# Power.net
KiCad netlist of a schematic drawn in Altium Designer
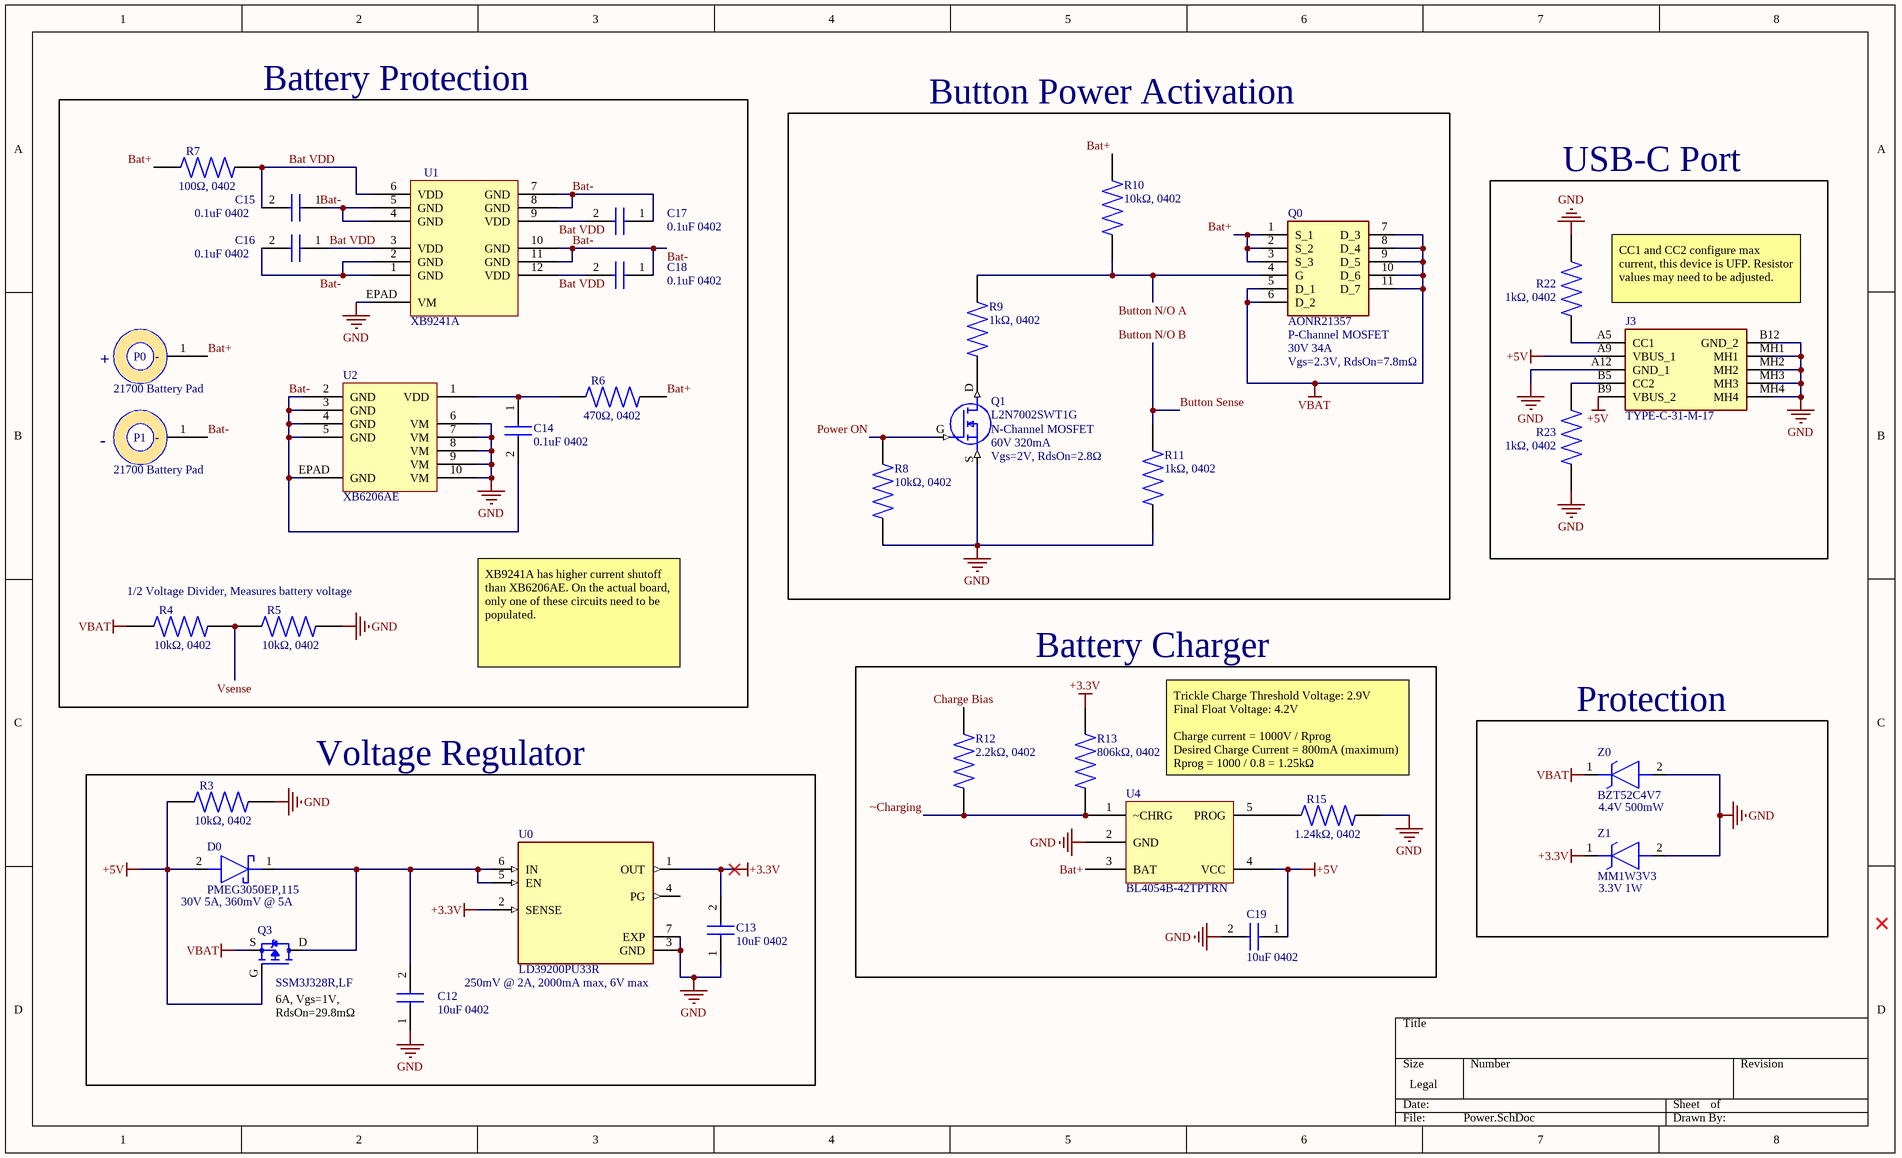
[diagram p0: Power.SchDoc]

(export (version "E")
  (design (tool "Eeschema 10.0.6"))
  (components
    (comp (ref "C12")
      (value "10uF 0402")
      (footprint "SamacSys:CAPC1005X56N")
      (description "Capacitor")
      (fields
        (field (name "MANUFACTURER_PART_NUMBER") "04025A100BAT2A")
        (field (name "MOUSER PART NUMBER") "581-04025A100B")
      )
      (libsource (lib "*") (part "04025A100BAT2A"))
    )
    (comp (ref "C13")
      (value "10uF 0402")
      (footprint "SamacSys:CAPC1005X56N")
      (description "Capacitor")
      (fields
        (field (name "MANUFACTURER_PART_NUMBER") "04025A100BAT2A")
        (field (name "MOUSER PART NUMBER") "581-04025A100B")
      )
      (libsource (lib "*") (part "04025A100BAT2A"))
    )
    (comp (ref "C14")
      (value "0.1uF 0402")
      (footprint "SamacSys:CAPC1005X56N")
      (description "Capacitor")
      (fields
        (field (name "MANUFACTURER_PART_NUMBER") "04025A100BAT2A")
        (field (name "MOUSER PART NUMBER") "581-04025A100B")
      )
      (libsource (lib "*") (part "04025A100BAT2A"))
    )
    (comp (ref "C15")
      (value "0.1uF 0402")
      (footprint "SamacSys:CAPC1005X56N")
      (description "Capacitor")
      (fields
        (field (name "MANUFACTURER_PART_NUMBER") "04025A100BAT2A")
        (field (name "MOUSER PART NUMBER") "581-04025A100B")
      )
      (libsource (lib "*") (part "04025A100BAT2A"))
    )
    (comp (ref "C16")
      (value "0.1uF 0402")
      (footprint "SamacSys:CAPC1005X56N")
      (description "Capacitor")
      (fields
        (field (name "MANUFACTURER_PART_NUMBER") "04025A100BAT2A")
        (field (name "MOUSER PART NUMBER") "581-04025A100B")
      )
      (libsource (lib "*") (part "04025A100BAT2A"))
    )
    (comp (ref "C17")
      (value "0.1uF 0402")
      (footprint "SamacSys:CAPC1005X56N")
      (description "Capacitor")
      (fields
        (field (name "MANUFACTURER_PART_NUMBER") "04025A100BAT2A")
        (field (name "MOUSER PART NUMBER") "581-04025A100B")
      )
      (libsource (lib "*") (part "04025A100BAT2A"))
    )
    (comp (ref "C18")
      (value "0.1uF 0402")
      (footprint "SamacSys:CAPC1005X56N")
      (description "Capacitor")
      (fields
        (field (name "MANUFACTURER_PART_NUMBER") "04025A100BAT2A")
        (field (name "MOUSER PART NUMBER") "581-04025A100B")
      )
      (libsource (lib "*") (part "04025A100BAT2A"))
    )
    (comp (ref "C19")
      (value "10uF 0402")
      (footprint "SamacSys:CAPC1005X56N")
      (description "Capacitor")
      (fields
        (field (name "MANUFACTURER_PART_NUMBER") "04025A100BAT2A")
        (field (name "MOUSER PART NUMBER") "581-04025A100B")
      )
      (libsource (lib "*") (part "04025A100BAT2A"))
    )
    (comp (ref "D0")
      (value "PMEG3050EP,115")
      (footprint "Lightsaber PCB Library:SOD128")
      (description "Schottky Diode")
      (fields (field (name "MOUSER PART NUMBER") "771-PMEG3050EP115"))
      (libsource (lib "Lightsaber") (part "PMEG3050EP,115"))
    )
    (comp (ref "J3")
      (value "TYPE-C-31-M-17")
      (footprint "SamacSys:TYPEC31M17")
      (description "Connector")
      (libsource (lib "*") (part "TYPE-C-31-M-17"))
    )
    (comp (ref "P0")
      (value "21700 Battery Pad")
      (footprint "21700 Battery Pad")
      (libsource (lib "Lightsaber") (part "21700 Battery Pad"))
    )
    (comp (ref "P1")
      (value "21700 Battery Pad")
      (footprint "21700 Battery Pad")
      (libsource (lib "Lightsaber") (part "21700 Battery Pad"))
    )
    (comp (ref "Q0")
      (value "AONR21357")
      (footprint "SamacSys:AONR21357")
      (description "MOSFET (P-Channel)")
      (libsource (lib "*") (part "AONR21357"))
    )
    (comp (ref "Q1")
      (value "L2N7002SWT1G")
      (footprint "Lightsaber PCB Library:SC-70")
      (description "MOSFET (N-Channel)")
      (fields
        (field (name "MANUFACTURER_PART_NUMBER") "2N7000")
        (field (name "MOUSER PART NUMBER") "512-2N7000")
      )
      (libsource (lib "Lightsaber") (part "L2N7002SWT1G"))
    )
    (comp (ref "Q3")
      (value "SSM3J328R,LF")
      (footprint "SOT-23F")
      (description "P-Channel 20V 9.4A (Ta) 2.4W (Ta) Surface Mount 6-MicroFET (2x2)")
      (fields (field (name "MP") "FDMA910PZ") (field (name "MF") "{'manufacturer': u'ON Semiconductor'}"))
      (libsource (lib "Lightsaber") (part "SSM3J328R,LF"))
    )
    (comp (ref "R3")
      (value "10kΩ, 0402")
      (footprint "0402")
      (libsource (lib "Lightsaber") (part "Resistor, 0402"))
    )
    (comp (ref "R4")
      (value "10kΩ, 0402")
      (footprint "0402")
      (libsource (lib "Lightsaber") (part "Resistor, 0402"))
    )
    (comp (ref "R5")
      (value "10kΩ, 0402")
      (footprint "0402")
      (libsource (lib "Lightsaber") (part "Resistor, 0402"))
    )
    (comp (ref "R6")
      (value "470Ω, 0402")
      (footprint "0402")
      (libsource (lib "Lightsaber") (part "Resistor, 0402"))
    )
    (comp (ref "R7")
      (value "100Ω, 0402")
      (footprint "0402")
      (libsource (lib "Lightsaber") (part "Resistor, 0402"))
    )
    (comp (ref "R8")
      (value "10kΩ, 0402")
      (footprint "0402")
      (libsource (lib "Lightsaber") (part "Resistor, 0402"))
    )
    (comp (ref "R9")
      (value "1kΩ, 0402")
      (footprint "0402")
      (libsource (lib "Lightsaber") (part "Resistor, 0402"))
    )
    (comp (ref "R10")
      (value "10kΩ, 0402")
      (footprint "0402")
      (libsource (lib "Lightsaber") (part "Resistor, 0402"))
    )
    (comp (ref "R11")
      (value "1kΩ, 0402")
      (footprint "0402")
      (libsource (lib "Lightsaber") (part "Resistor, 0402"))
    )
    (comp (ref "R12")
      (value "2.2kΩ, 0402")
      (footprint "0402")
      (libsource (lib "Lightsaber") (part "Resistor, 0402"))
    )
    (comp (ref "R13")
      (value "806kΩ, 0402")
      (footprint "0402")
      (libsource (lib "Lightsaber") (part "Resistor, 0402"))
    )
    (comp (ref "R15")
      (value "1.24kΩ, 0402")
      (footprint "0402")
      (libsource (lib "Lightsaber") (part "Resistor, 0402"))
    )
    (comp (ref "R22")
      (value "1kΩ, 0402")
      (footprint "0402")
      (libsource (lib "Lightsaber") (part "Resistor, 0402"))
    )
    (comp (ref "R23")
      (value "1kΩ, 0402")
      (footprint "0402")
      (libsource (lib "Lightsaber") (part "Resistor, 0402"))
    )
    (comp (ref "U0")
      (value "LD39200PU33R")
      (footprint "LD39200PU33R:SON95P300X300X100-7N")
      (description "Linear Voltage Regulator IC 1 Output 2A 6-DFN (3x3)")
      (fields (field (name "MF") "{'manufacturer': u'STMicroelectronics'}"))
      (libsource (lib "*") (part "LD39200PU33R"))
    )
    (comp (ref "U1")
      (value "XB9241A")
      (footprint "DFN4x4x0.55-12FC")
      (libsource (lib "Lightsaber") (part "XB9241A"))
    )
    (comp (ref "U2")
      (value "XB6206AE")
      (footprint "DFN3X3-10")
      (libsource (lib "Lightsaber") (part "XB6206AE"))
    )
    (comp (ref "U4")
      (value "BL4054B-42TPTRN")
      (footprint "TSOT23-5")
      (libsource (lib "Lightsaber") (part "BL4054B-42TPTRN"))
    )
    (comp (ref "Z0")
      (value "BZT52C4V7")
      (footprint "Lightsaber PCB Library:SOD-123")
      (description "Zener Diode")
      (fields
        (field (name "MANUFACTURER_PART_NUMBER") "BZT52-B5V1J")
        (field (name "MOUSER PART NUMBER") "771-BZT52-B5V1J")
      )
      (libsource (lib "Lightsaber") (part "BZT52C4V7"))
    )
    (comp (ref "Z1")
      (value "MM1W3V3")
      (footprint "Lightsaber PCB Library:SOD-123")
      (description "Zener Diode")
      (fields
        (field (name "MANUFACTURER_PART_NUMBER") "BZT52-B5V1J")
        (field (name "MOUSER PART NUMBER") "771-BZT52-B5V1J")
      )
      (libsource (lib "Lightsaber") (part "MM1W3V3"))
    )
  )
  (nets
    (net (code "1") (name "+3.3V") (class "Default")
      (node (ref "C13") (pin "2") (pinfunction "2_2") (pintype "passive"))
      (node (ref "R13") (pin "2") (pinfunction "2_2") (pintype "passive"))
      (node (ref "U0") (pin "1") (pinfunction "OUT_1") (pintype "output"))
      (node (ref "U0") (pin "2") (pinfunction "SENSE_2") (pintype "input"))
      (node (ref "Z1") (pin "1") (pinfunction "K_1") (pintype "passive"))
    )
    (net (code "2") (name "+5V") (class "Default")
      (node (ref "C19") (pin "1") (pinfunction "1_1") (pintype "passive"))
      (node (ref "D0") (pin "2") (pinfunction "A_2") (pintype "passive"))
      (node (ref "J3") (pin "A9") (pinfunction "VBUS_1_A9") (pintype "passive"))
      (node (ref "J3") (pin "B9") (pinfunction "VBUS_2_B9") (pintype "passive"))
      (node (ref "Q3") (pin "G") (pinfunction "G_G") (pintype "passive"))
      (node (ref "R3") (pin "1") (pinfunction "1_1") (pintype "passive"))
      (node (ref "U4") (pin "4") (pinfunction "VCC_4") (pintype "passive"))
    )
    (net (code "3") (name "/Bat VDD") (class "Default")
      (node (ref "C15") (pin "2") (pinfunction "2_2") (pintype "passive"))
      (node (ref "C16") (pin "1") (pinfunction "1_1") (pintype "passive"))
      (node (ref "C17") (pin "2") (pinfunction "2_2") (pintype "passive"))
      (node (ref "C18") (pin "2") (pinfunction "2_2") (pintype "passive"))
      (node (ref "R7") (pin "2") (pinfunction "2_2") (pintype "passive"))
      (node (ref "U1") (pin "12") (pinfunction "VDD_12") (pintype "passive"))
      (node (ref "U1") (pin "3") (pinfunction "VDD_3") (pintype "passive"))
      (node (ref "U1") (pin "6") (pinfunction "VDD_6") (pintype "passive"))
      (node (ref "U1") (pin "9") (pinfunction "VDD_9") (pintype "passive"))
    )
    (net (code "4") (name "/Bat+") (class "Default")
      (node (ref "P0") (pin "1") (pinfunction "-_1") (pintype "passive"))
      (node (ref "Q0") (pin "1") (pinfunction "S_1_1") (pintype "passive"))
      (node (ref "Q0") (pin "2") (pinfunction "S_2_2") (pintype "passive"))
      (node (ref "Q0") (pin "3") (pinfunction "S_3_3") (pintype "passive"))
      (node (ref "R10") (pin "2") (pinfunction "2_2") (pintype "passive"))
      (node (ref "R6") (pin "2") (pinfunction "2_2") (pintype "passive"))
      (node (ref "R7") (pin "1") (pinfunction "1_1") (pintype "passive"))
      (node (ref "U4") (pin "3") (pinfunction "BAT_3") (pintype "passive"))
    )
    (net (code "5") (name "/Bat-") (class "Default")
      (node (ref "C14") (pin "2") (pinfunction "2_2") (pintype "passive"))
      (node (ref "C15") (pin "1") (pinfunction "1_1") (pintype "passive"))
      (node (ref "C16") (pin "2") (pinfunction "2_2") (pintype "passive"))
      (node (ref "C17") (pin "1") (pinfunction "1_1") (pintype "passive"))
      (node (ref "C18") (pin "1") (pinfunction "1_1") (pintype "passive"))
      (node (ref "P1") (pin "1") (pinfunction "-_1") (pintype "passive"))
      (node (ref "U1") (pin "1") (pinfunction "GND_1") (pintype "passive"))
      (node (ref "U1") (pin "10") (pinfunction "GND_10") (pintype "passive"))
      (node (ref "U1") (pin "11") (pinfunction "GND_11") (pintype "passive"))
      (node (ref "U1") (pin "2") (pinfunction "GND_2") (pintype "passive"))
      (node (ref "U1") (pin "4") (pinfunction "GND_4") (pintype "passive"))
      (node (ref "U1") (pin "5") (pinfunction "GND_5") (pintype "passive"))
      (node (ref "U1") (pin "7") (pinfunction "GND_7") (pintype "passive"))
      (node (ref "U1") (pin "8") (pinfunction "GND_8") (pintype "passive"))
      (node (ref "U2") (pin "2") (pinfunction "GND_2") (pintype "passive"))
      (node (ref "U2") (pin "3") (pinfunction "GND_3") (pintype "passive"))
      (node (ref "U2") (pin "4") (pinfunction "GND_4") (pintype "passive"))
      (node (ref "U2") (pin "5") (pinfunction "GND_5") (pintype "passive"))
      (node (ref "U2") (pin "EPAD") (pinfunction "GND_EPAD") (pintype "passive"))
    )
    (net (code "6") (name "/Button N{slash}O A") (class "Default")
      (node (ref "Q0") (pin "4") (pinfunction "G_4") (pintype "passive"))
      (node (ref "R10") (pin "1") (pinfunction "1_1") (pintype "passive"))
      (node (ref "R9") (pin "2") (pinfunction "2_2") (pintype "passive"))
    )
    (net (code "7") (name "/Button N{slash}O B") (class "Default")
      (node (ref "R11") (pin "2") (pinfunction "2_2") (pintype "passive"))
    )
    (net (code "8") (name "/Charge Bias") (class "Default")
      (node (ref "R12") (pin "2") (pinfunction "2_2") (pintype "passive"))
    )
    (net (code "9") (name "/Power ON") (class "Default")
      (node (ref "Q1") (pin "G") (pinfunction "G_G") (pintype "input"))
      (node (ref "R8") (pin "2") (pinfunction "2_2") (pintype "passive"))
    )
    (net (code "10") (name "/Vsense") (class "Default")
      (node (ref "R4") (pin "2") (pinfunction "2_2") (pintype "passive"))
      (node (ref "R5") (pin "1") (pinfunction "1_1") (pintype "passive"))
    )
    (net (code "11") (name "/~Charging") (class "Default")
      (node (ref "R12") (pin "1") (pinfunction "1_1") (pintype "passive"))
      (node (ref "R13") (pin "1") (pinfunction "1_1") (pintype "passive"))
      (node (ref "U4") (pin "1") (pinfunction "~CHRG_1") (pintype "passive"))
    )
    (net (code "12") (name "GND") (class "Default")
      (node (ref "C12") (pin "1") (pinfunction "1_1") (pintype "passive"))
      (node (ref "C13") (pin "1") (pinfunction "1_1") (pintype "passive"))
      (node (ref "C19") (pin "2") (pinfunction "2_2") (pintype "passive"))
      (node (ref "J3") (pin "A12") (pinfunction "GND_1_A12") (pintype "passive"))
      (node (ref "J3") (pin "B12") (pinfunction "GND_2_B12") (pintype "passive"))
      (node (ref "J3") (pin "MH1") (pinfunction "MH1_MH1") (pintype "passive"))
      (node (ref "J3") (pin "MH2") (pinfunction "MH2_MH2") (pintype "passive"))
      (node (ref "J3") (pin "MH3") (pinfunction "MH3_MH3") (pintype "passive"))
      (node (ref "J3") (pin "MH4") (pinfunction "MH4_MH4") (pintype "passive"))
      (node (ref "Q1") (pin "S") (pinfunction "S_S") (pintype "input"))
      (node (ref "R11") (pin "1") (pinfunction "1_1") (pintype "passive"))
      (node (ref "R15") (pin "2") (pinfunction "2_2") (pintype "passive"))
      (node (ref "R22") (pin "2") (pinfunction "2_2") (pintype "passive"))
      (node (ref "R23") (pin "1") (pinfunction "1_1") (pintype "passive"))
      (node (ref "R3") (pin "2") (pinfunction "2_2") (pintype "passive"))
      (node (ref "R5") (pin "2") (pinfunction "2_2") (pintype "passive"))
      (node (ref "R8") (pin "1") (pinfunction "1_1") (pintype "passive"))
      (node (ref "U0") (pin "3") (pinfunction "GND_3") (pintype "power_in"))
      (node (ref "U0") (pin "7") (pinfunction "EXP_7") (pintype "power_in"))
      (node (ref "U1") (pin "EPAD") (pinfunction "VM_EPAD") (pintype "passive"))
      (node (ref "U2") (pin "10") (pinfunction "VM_10") (pintype "passive"))
      (node (ref "U2") (pin "6") (pinfunction "VM_6") (pintype "passive"))
      (node (ref "U2") (pin "7") (pinfunction "VM_7") (pintype "passive"))
      (node (ref "U2") (pin "8") (pinfunction "VM_8") (pintype "passive"))
      (node (ref "U2") (pin "9") (pinfunction "VM_9") (pintype "passive"))
      (node (ref "U4") (pin "2") (pinfunction "GND_2") (pintype "passive"))
      (node (ref "Z0") (pin "2") (pinfunction "A_2") (pintype "passive"))
      (node (ref "Z1") (pin "2") (pinfunction "A_2") (pintype "passive"))
    )
    (net (code "13") (name "Net-(D0-K)") (class "Default")
      (node (ref "C12") (pin "2") (pinfunction "2_2") (pintype "passive"))
      (node (ref "D0") (pin "1") (pinfunction "K_1") (pintype "passive"))
      (node (ref "Q3") (pin "D") (pinfunction "D_D") (pintype "passive"))
      (node (ref "U0") (pin "5") (pinfunction "EN_5") (pintype "input"))
      (node (ref "U0") (pin "6") (pinfunction "IN_6") (pintype "input"))
    )
    (net (code "14") (name "Net-(J3-CC1)") (class "Default")
      (node (ref "J3") (pin "A5") (pinfunction "CC1_A5") (pintype "passive"))
      (node (ref "R22") (pin "1") (pinfunction "1_1") (pintype "passive"))
    )
    (net (code "15") (name "Net-(J3-CC2)") (class "Default")
      (node (ref "J3") (pin "B5") (pinfunction "CC2_B5") (pintype "passive"))
      (node (ref "R23") (pin "2") (pinfunction "2_2") (pintype "passive"))
    )
    (net (code "16") (name "Net-(Q1-PadD)") (class "Default")
      (node (ref "Q1") (pin "D") (pinfunction "D_D") (pintype "output"))
      (node (ref "R9") (pin "1") (pinfunction "1_1") (pintype "passive"))
    )
    (net (code "17") (name "Net-(U2-VDD)") (class "Default")
      (node (ref "C14") (pin "1") (pinfunction "1_1") (pintype "passive"))
      (node (ref "R6") (pin "1") (pinfunction "1_1") (pintype "passive"))
      (node (ref "U2") (pin "1") (pinfunction "VDD_1") (pintype "passive"))
    )
    (net (code "18") (name "Net-(U4-PROG)") (class "Default")
      (node (ref "R15") (pin "1") (pinfunction "1_1") (pintype "passive"))
      (node (ref "U4") (pin "5") (pinfunction "PROG_5") (pintype "passive"))
    )
    (net (code "19") (name "VBAT") (class "Default")
      (node (ref "Q0") (pin "10") (pinfunction "D_6_10") (pintype "passive"))
      (node (ref "Q0") (pin "11") (pinfunction "D_7_11") (pintype "passive"))
      (node (ref "Q0") (pin "5") (pinfunction "D_1_5") (pintype "passive"))
      (node (ref "Q0") (pin "6") (pinfunction "D_2_6") (pintype "passive"))
      (node (ref "Q0") (pin "7") (pinfunction "D_3_7") (pintype "passive"))
      (node (ref "Q0") (pin "8") (pinfunction "D_4_8") (pintype "passive"))
      (node (ref "Q0") (pin "9") (pinfunction "D_5_9") (pintype "passive"))
      (node (ref "Q3") (pin "S") (pinfunction "S_S") (pintype "passive"))
      (node (ref "R4") (pin "1") (pinfunction "1_1") (pintype "passive"))
      (node (ref "Z0") (pin "1") (pinfunction "K_1") (pintype "passive"))
    )
    (net (code "20") (name "unconnected-(U0-PG-Pad4)") (class "Default")
      (node (ref "U0") (pin "4") (pinfunction "PG_4") (pintype "output"))
    )
  )
)
